# Sheet.net
KiCad netlist of a schematic drawn in Altium Designer
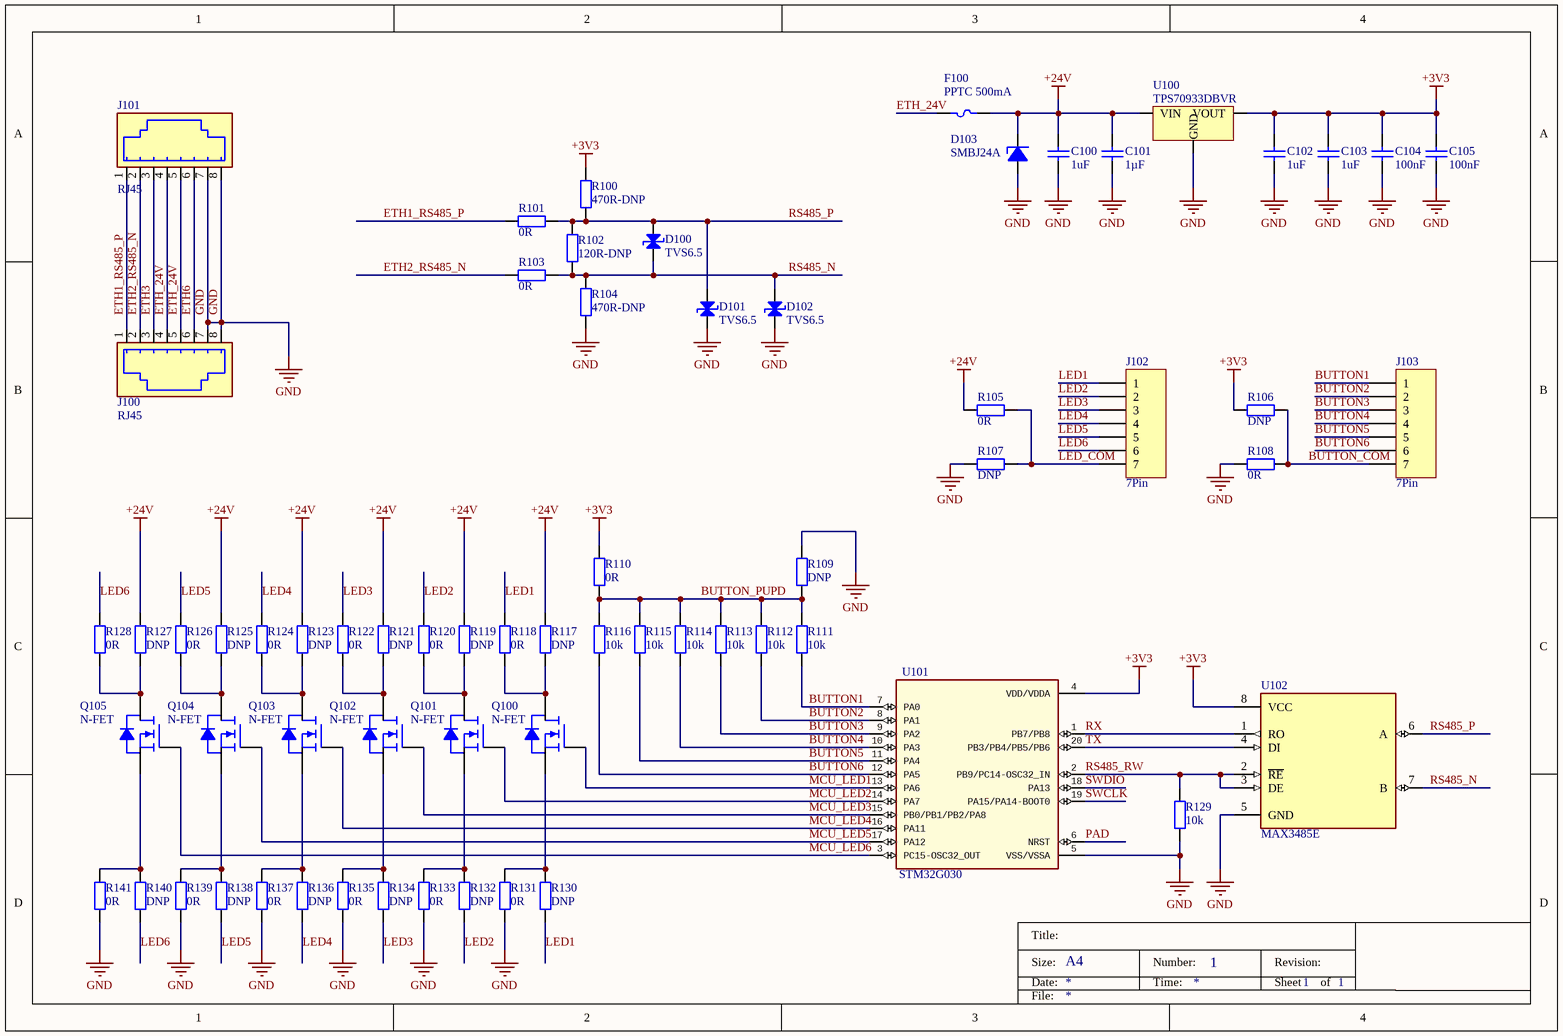
[diagram p0: Sheet.SchDoc]

(export (version "E")
  (design (tool "Eeschema 10.0.6"))
  (components
    (comp (ref "C100") (value "1uF") (footprint "C0603") (libsource (lib "Library") (part "Capacitor")))
    (comp (ref "C101") (value "1µF") (footprint "C0603") (libsource (lib "Library") (part "Capacitor")))
    (comp (ref "C102") (value "1uF") (footprint "C0603") (libsource (lib "Library") (part "Capacitor")))
    (comp (ref "C103") (value "1uF") (footprint "C0603") (libsource (lib "Library") (part "Capacitor")))
    (comp (ref "C104") (value "100nF") (footprint "C0603") (libsource (lib "Library") (part "Capacitor")))
    (comp (ref "C105") (value "100nF") (footprint "C0603") (libsource (lib "Library") (part "Capacitor")))
    (comp (ref "D100") (value "TVS6.5") (footprint "SOD323") (libsource (lib "Library") (part "TVS Bi")))
    (comp (ref "D101") (value "TVS6.5") (footprint "SOD323") (libsource (lib "Library") (part "TVS Bi")))
    (comp (ref "D102") (value "TVS6.5") (footprint "SOD323") (libsource (lib "Library") (part "TVS Bi")))
    (comp (ref "D103") (value "SMBJ24A") (footprint "SMB") (libsource (lib "Library") (part "TVS Uni")))
    (comp (ref "F100") (value "PPTC 500mA") (footprint "PPTC1812") (libsource (lib "Library") (part "Fuse")))
    (comp (ref "J100")
      (value "RJ45")
      (footprint "RJ45_RA")
      (description "Jack Modular Connector 8p8c (RJ45, Ethernet) Vertical Unshielded Cat5")
      (fields (field (name "MF") "Wurth Elektronik") (field (name "MP") "615008144221"))
      (libsource (lib "Library") (part "RJ45"))
    )
    (comp (ref "J101")
      (value "RJ45")
      (footprint "RJ45_RA")
      (description "Jack Modular Connector 8p8c (RJ45, Ethernet) Vertical Unshielded Cat5")
      (fields (field (name "MF") "Wurth Elektronik") (field (name "MP") "615008144221"))
      (libsource (lib "") (part "RJ45_1"))
    )
    (comp (ref "J102") (value "7Pin") (footprint "7Pin") (libsource (lib "Library") (part "7Pin")))
    (comp (ref "J103") (value "7Pin") (footprint "7Pin") (libsource (lib "Library") (part "7Pin")))
    (comp (ref "Q100") (value "N-FET") (footprint "SOT323") (libsource (lib "Library") (part "N-FET")))
    (comp (ref "Q101") (value "N-FET") (footprint "SOT323") (libsource (lib "Library") (part "N-FET")))
    (comp (ref "Q102") (value "N-FET") (footprint "SOT323") (libsource (lib "Library") (part "N-FET")))
    (comp (ref "Q103") (value "N-FET") (footprint "SOT323") (libsource (lib "Library") (part "N-FET")))
    (comp (ref "Q104") (value "N-FET") (footprint "SOT323") (libsource (lib "Library") (part "N-FET")))
    (comp (ref "Q105") (value "N-FET") (footprint "SOT323") (libsource (lib "Library") (part "N-FET")))
    (comp (ref "R100") (value "470R-DNP") (footprint "R0603") (libsource (lib "") (part "Resistor_1")))
    (comp (ref "R101") (value "0R") (footprint "R0603") (libsource (lib "Library") (part "Resistor")))
    (comp (ref "R102") (value "120R-DNP") (footprint "R0603") (libsource (lib "") (part "Resistor_1")))
    (comp (ref "R103") (value "0R") (footprint "R0603") (libsource (lib "Library") (part "Resistor")))
    (comp (ref "R104") (value "470R-DNP") (footprint "R0603") (libsource (lib "") (part "Resistor_1")))
    (comp (ref "R105") (value "0R") (footprint "R0603") (libsource (lib "") (part "Resistor_2")))
    (comp (ref "R106") (value "DNP") (footprint "R0603") (libsource (lib "") (part "Resistor_2")))
    (comp (ref "R107") (value "DNP") (footprint "R0603") (libsource (lib "") (part "Resistor_2")))
    (comp (ref "R108") (value "0R") (footprint "R0603") (libsource (lib "") (part "Resistor_2")))
    (comp (ref "R109") (value "DNP") (footprint "R0603") (libsource (lib "Library") (part "Resistor")))
    (comp (ref "R110") (value "0R") (footprint "R0603") (libsource (lib "Library") (part "Resistor")))
    (comp (ref "R111") (value "10k") (footprint "R0603") (libsource (lib "Library") (part "Resistor")))
    (comp (ref "R112") (value "10k") (footprint "R0603") (libsource (lib "Library") (part "Resistor")))
    (comp (ref "R113") (value "10k") (footprint "R0603") (libsource (lib "Library") (part "Resistor")))
    (comp (ref "R114") (value "10k") (footprint "R0603") (libsource (lib "Library") (part "Resistor")))
    (comp (ref "R115") (value "10k") (footprint "R0603") (libsource (lib "Library") (part "Resistor")))
    (comp (ref "R116") (value "10k") (footprint "R0603") (libsource (lib "Library") (part "Resistor")))
    (comp (ref "R117") (value "DNP") (footprint "R0603") (libsource (lib "Library") (part "Resistor")))
    (comp (ref "R118") (value "0R") (footprint "R0603") (libsource (lib "Library") (part "Resistor")))
    (comp (ref "R119") (value "DNP") (footprint "R0603") (libsource (lib "Library") (part "Resistor")))
    (comp (ref "R120") (value "0R") (footprint "R0603") (libsource (lib "Library") (part "Resistor")))
    (comp (ref "R121") (value "DNP") (footprint "R0603") (libsource (lib "Library") (part "Resistor")))
    (comp (ref "R122") (value "0R") (footprint "R0603") (libsource (lib "Library") (part "Resistor")))
    (comp (ref "R123") (value "DNP") (footprint "R0603") (libsource (lib "Library") (part "Resistor")))
    (comp (ref "R124") (value "0R") (footprint "R0603") (libsource (lib "Library") (part "Resistor")))
    (comp (ref "R125") (value "DNP") (footprint "R0603") (libsource (lib "Library") (part "Resistor")))
    (comp (ref "R126") (value "0R") (footprint "R0603") (libsource (lib "Library") (part "Resistor")))
    (comp (ref "R127") (value "DNP") (footprint "R0603") (libsource (lib "Library") (part "Resistor")))
    (comp (ref "R128") (value "0R") (footprint "R0603") (libsource (lib "Library") (part "Resistor")))
    (comp (ref "R129") (value "10k") (footprint "R0603") (libsource (lib "Library") (part "Resistor")))
    (comp (ref "R130") (value "DNP") (footprint "R0603") (libsource (lib "Library") (part "Resistor")))
    (comp (ref "R131") (value "0R") (footprint "R0603") (libsource (lib "Library") (part "Resistor")))
    (comp (ref "R132") (value "DNP") (footprint "R0603") (libsource (lib "Library") (part "Resistor")))
    (comp (ref "R133") (value "0R") (footprint "R0603") (libsource (lib "Library") (part "Resistor")))
    (comp (ref "R134") (value "DNP") (footprint "R0603") (libsource (lib "Library") (part "Resistor")))
    (comp (ref "R135") (value "0R") (footprint "R0603") (libsource (lib "Library") (part "Resistor")))
    (comp (ref "R136") (value "DNP") (footprint "R0603") (libsource (lib "Library") (part "Resistor")))
    (comp (ref "R137") (value "0R") (footprint "R0603") (libsource (lib "Library") (part "Resistor")))
    (comp (ref "R138") (value "DNP") (footprint "R0603") (libsource (lib "Library") (part "Resistor")))
    (comp (ref "R139") (value "0R") (footprint "R0603") (libsource (lib "Library") (part "Resistor")))
    (comp (ref "R140") (value "DNP") (footprint "R0603") (libsource (lib "Library") (part "Resistor")))
    (comp (ref "R141") (value "0R") (footprint "R0603") (libsource (lib "Library") (part "Resistor")))
    (comp (ref "U100")
      (value "TPS70933DBVR")
      (footprint "SOT-23-5")
      (fields (field (name "MP") "LP38690DT-5.0/NOPB") (field (name "MF") "Texas Instruments"))
      (libsource (lib "Schlib1") (part "LDO"))
    )
    (comp (ref "U101")
      (value "STM32G030")
      (footprint "TSSOP20")
      (fields
        (field (name "MANUFACTURER_PART_NUMBER") "STM32G030F6P6TR")
        (field (name "COPYRIGHT") "Copyright (C) 2022 Ultra Librarian. All rights reserved.")
      )
      (libsource (lib "Schlib1") (part "STM32G030"))
    )
    (comp (ref "U102")
      (value "MAX3485E")
      (footprint "SOIC-08")
      (description "1/1 Transceiver Half RS422, RS485 8-SOIC")
      (fields (field (name "MF") "Maxim Integrated") (field (name "MP") "MAX3485EESA+T"))
      (libsource (lib "Library") (part "MAX3485E"))
    )
  )
  (nets
    (net (code "1") (name "+3V3") (class "Default")
      (node (ref "C102") (pin "2") (pinfunction "2_2") (pintype "passive"))
      (node (ref "C103") (pin "2") (pinfunction "2_2") (pintype "passive"))
      (node (ref "C104") (pin "2") (pinfunction "2_2") (pintype "passive"))
      (node (ref "C105") (pin "2") (pinfunction "2_2") (pintype "passive"))
      (node (ref "R100") (pin "2") (pinfunction "2_2") (pintype "passive"))
      (node (ref "R106") (pin "2") (pinfunction "2_2") (pintype "passive"))
      (node (ref "R110") (pin "2") (pinfunction "2_2") (pintype "passive"))
      (node (ref "U100") (pin "5") (pinfunction "VOUT_5") (pintype "power_in"))
      (node (ref "U101") (pin "4") (pinfunction "VDD/VDDA_4") (pintype "power_in"))
      (node (ref "U102") (pin "8") (pinfunction "VCC_8") (pintype "power_in"))
    )
    (net (code "2") (name "+24V") (class "Default")
      (node (ref "C100") (pin "2") (pinfunction "2_2") (pintype "passive"))
      (node (ref "C101") (pin "2") (pinfunction "2_2") (pintype "passive"))
      (node (ref "D103") (pin "1") (pinfunction "1_1") (pintype "passive"))
      (node (ref "F100") (pin "2") (pinfunction "2_2") (pintype "passive"))
      (node (ref "R105") (pin "2") (pinfunction "2_2") (pintype "passive"))
      (node (ref "R117") (pin "2") (pinfunction "2_2") (pintype "passive"))
      (node (ref "R119") (pin "2") (pinfunction "2_2") (pintype "passive"))
      (node (ref "R121") (pin "2") (pinfunction "2_2") (pintype "passive"))
      (node (ref "R123") (pin "2") (pinfunction "2_2") (pintype "passive"))
      (node (ref "R125") (pin "2") (pinfunction "2_2") (pintype "passive"))
      (node (ref "R127") (pin "2") (pinfunction "2_2") (pintype "passive"))
      (node (ref "U100") (pin "1") (pinfunction "VIN_1") (pintype "power_in"))
    )
    (net (code "3") (name "/BUTTON1") (class "Default")
      (node (ref "J103") (pin "1") (pinfunction "1_1") (pintype "passive"))
      (node (ref "R111") (pin "1") (pinfunction "1_1") (pintype "passive"))
      (node (ref "U101") (pin "7") (pinfunction "PA0_7") (pintype "bidirectional"))
    )
    (net (code "4") (name "/BUTTON2") (class "Default")
      (node (ref "J103") (pin "2") (pinfunction "2_2") (pintype "passive"))
      (node (ref "R112") (pin "1") (pinfunction "1_1") (pintype "passive"))
      (node (ref "U101") (pin "8") (pinfunction "PA1_8") (pintype "bidirectional"))
    )
    (net (code "5") (name "/BUTTON3") (class "Default")
      (node (ref "J103") (pin "3") (pinfunction "3_3") (pintype "passive"))
      (node (ref "R113") (pin "1") (pinfunction "1_1") (pintype "passive"))
      (node (ref "U101") (pin "9") (pinfunction "PA2_9") (pintype "bidirectional"))
    )
    (net (code "6") (name "/BUTTON4") (class "Default")
      (node (ref "J103") (pin "4") (pinfunction "4_4") (pintype "passive"))
      (node (ref "R114") (pin "1") (pinfunction "1_1") (pintype "passive"))
      (node (ref "U101") (pin "10") (pinfunction "PA3_10") (pintype "bidirectional"))
    )
    (net (code "7") (name "/BUTTON5") (class "Default")
      (node (ref "J103") (pin "5") (pinfunction "5_5") (pintype "passive"))
      (node (ref "R115") (pin "1") (pinfunction "1_1") (pintype "passive"))
      (node (ref "U101") (pin "11") (pinfunction "PA4_11") (pintype "bidirectional"))
    )
    (net (code "8") (name "/BUTTON6") (class "Default")
      (node (ref "J103") (pin "6") (pinfunction "6_6") (pintype "passive"))
      (node (ref "R116") (pin "1") (pinfunction "1_1") (pintype "passive"))
      (node (ref "U101") (pin "12") (pinfunction "PA5_12") (pintype "bidirectional"))
    )
    (net (code "9") (name "/BUTTON_COM") (class "Default")
      (node (ref "J103") (pin "7") (pinfunction "7_7") (pintype "passive"))
      (node (ref "R106") (pin "1") (pinfunction "1_1") (pintype "passive"))
      (node (ref "R108") (pin "1") (pinfunction "1_1") (pintype "passive"))
    )
    (net (code "10") (name "/BUTTON_PUPD") (class "Default")
      (node (ref "R109") (pin "1") (pinfunction "1_1") (pintype "passive"))
      (node (ref "R110") (pin "1") (pinfunction "1_1") (pintype "passive"))
      (node (ref "R111") (pin "2") (pinfunction "2_2") (pintype "passive"))
      (node (ref "R112") (pin "2") (pinfunction "2_2") (pintype "passive"))
      (node (ref "R113") (pin "2") (pinfunction "2_2") (pintype "passive"))
      (node (ref "R114") (pin "2") (pinfunction "2_2") (pintype "passive"))
      (node (ref "R115") (pin "2") (pinfunction "2_2") (pintype "passive"))
      (node (ref "R116") (pin "2") (pinfunction "2_2") (pintype "passive"))
    )
    (net (code "11") (name "/ETH1_RS485_P") (class "Default")
      (node (ref "J100") (pin "1") (pinfunction "8_1") (pintype "passive"))
      (node (ref "J101") (pin "1") (pinfunction "8_1") (pintype "passive"))
      (node (ref "R101") (pin "1") (pinfunction "1_1") (pintype "passive"))
    )
    (net (code "12") (name "/ETH2_RS485_N") (class "Default")
      (node (ref "J100") (pin "2") (pinfunction "7_2") (pintype "passive"))
      (node (ref "J101") (pin "2") (pinfunction "7_2") (pintype "passive"))
      (node (ref "R103") (pin "1") (pinfunction "1_1") (pintype "passive"))
    )
    (net (code "13") (name "/ETH3") (class "Default")
      (node (ref "J100") (pin "3") (pinfunction "6_3") (pintype "passive"))
      (node (ref "J101") (pin "3") (pinfunction "6_3") (pintype "passive"))
    )
    (net (code "14") (name "/ETH6") (class "Default")
      (node (ref "J100") (pin "6") (pinfunction "3_6") (pintype "passive"))
      (node (ref "J101") (pin "6") (pinfunction "3_6") (pintype "passive"))
    )
    (net (code "15") (name "/ETH_24V") (class "Default")
      (node (ref "F100") (pin "1") (pinfunction "1_1") (pintype "passive"))
      (node (ref "J100") (pin "4") (pinfunction "5_4") (pintype "passive"))
      (node (ref "J100") (pin "5") (pinfunction "4_5") (pintype "passive"))
      (node (ref "J101") (pin "4") (pinfunction "5_4") (pintype "passive"))
      (node (ref "J101") (pin "5") (pinfunction "4_5") (pintype "passive"))
    )
    (net (code "16") (name "/LED1") (class "Default")
      (node (ref "J102") (pin "1") (pinfunction "1_1") (pintype "passive"))
      (node (ref "R118") (pin "2") (pinfunction "2_2") (pintype "passive"))
      (node (ref "R130") (pin "1") (pinfunction "1_1") (pintype "passive"))
    )
    (net (code "17") (name "/LED2") (class "Default")
      (node (ref "J102") (pin "2") (pinfunction "2_2") (pintype "passive"))
      (node (ref "R120") (pin "2") (pinfunction "2_2") (pintype "passive"))
      (node (ref "R132") (pin "1") (pinfunction "1_1") (pintype "passive"))
    )
    (net (code "18") (name "/LED3") (class "Default")
      (node (ref "J102") (pin "3") (pinfunction "3_3") (pintype "passive"))
      (node (ref "R122") (pin "2") (pinfunction "2_2") (pintype "passive"))
      (node (ref "R134") (pin "1") (pinfunction "1_1") (pintype "passive"))
    )
    (net (code "19") (name "/LED4") (class "Default")
      (node (ref "J102") (pin "4") (pinfunction "4_4") (pintype "passive"))
      (node (ref "R124") (pin "2") (pinfunction "2_2") (pintype "passive"))
      (node (ref "R136") (pin "1") (pinfunction "1_1") (pintype "passive"))
    )
    (net (code "20") (name "/LED5") (class "Default")
      (node (ref "J102") (pin "5") (pinfunction "5_5") (pintype "passive"))
      (node (ref "R126") (pin "2") (pinfunction "2_2") (pintype "passive"))
      (node (ref "R138") (pin "1") (pinfunction "1_1") (pintype "passive"))
    )
    (net (code "21") (name "/LED6") (class "Default")
      (node (ref "J102") (pin "6") (pinfunction "6_6") (pintype "passive"))
      (node (ref "R128") (pin "2") (pinfunction "2_2") (pintype "passive"))
      (node (ref "R140") (pin "1") (pinfunction "1_1") (pintype "passive"))
    )
    (net (code "22") (name "/LED_COM") (class "Default")
      (node (ref "J102") (pin "7") (pinfunction "7_7") (pintype "passive"))
      (node (ref "R105") (pin "1") (pinfunction "1_1") (pintype "passive"))
      (node (ref "R107") (pin "1") (pinfunction "1_1") (pintype "passive"))
    )
    (net (code "23") (name "/MCU_LED1") (class "Default")
      (node (ref "Q100") (pin "1") (pinfunction "G_1") (pintype "passive"))
      (node (ref "U101") (pin "13") (pinfunction "PA6_13") (pintype "bidirectional"))
    )
    (net (code "24") (name "/MCU_LED2") (class "Default")
      (node (ref "Q101") (pin "1") (pinfunction "G_1") (pintype "passive"))
      (node (ref "U101") (pin "14") (pinfunction "PA7_14") (pintype "bidirectional"))
    )
    (net (code "25") (name "/MCU_LED3") (class "Default")
      (node (ref "Q102") (pin "1") (pinfunction "G_1") (pintype "passive"))
      (node (ref "U101") (pin "15") (pinfunction "PB0/PB1/PB2/PA8_15") (pintype "bidirectional"))
    )
    (net (code "26") (name "/MCU_LED4") (class "Default")
      (node (ref "Q103") (pin "1") (pinfunction "G_1") (pintype "passive"))
      (node (ref "U101") (pin "16") (pinfunction "PA11_16") (pintype "bidirectional"))
    )
    (net (code "27") (name "/MCU_LED5") (class "Default")
      (node (ref "Q104") (pin "1") (pinfunction "G_1") (pintype "passive"))
      (node (ref "U101") (pin "17") (pinfunction "PA12_17") (pintype "bidirectional"))
    )
    (net (code "28") (name "/MCU_LED6") (class "Default")
      (node (ref "Q105") (pin "1") (pinfunction "G_1") (pintype "passive"))
      (node (ref "U101") (pin "3") (pinfunction "PC15-OSC32_OUT_3") (pintype "bidirectional"))
    )
    (net (code "29") (name "/PAD") (class "Default")
      (node (ref "U101") (pin "6") (pinfunction "NRST_6") (pintype "bidirectional"))
    )
    (net (code "30") (name "/RS485_N") (class "Default")
      (node (ref "D100") (pin "1") (pinfunction "1_1") (pintype "passive"))
      (node (ref "D102") (pin "2") (pinfunction "2_2") (pintype "passive"))
      (node (ref "R102") (pin "1") (pinfunction "1_1") (pintype "passive"))
      (node (ref "R103") (pin "2") (pinfunction "2_2") (pintype "passive"))
      (node (ref "R104") (pin "2") (pinfunction "2_2") (pintype "passive"))
      (node (ref "U102") (pin "7") (pinfunction "B_7") (pintype "bidirectional"))
    )
    (net (code "31") (name "/RS485_P") (class "Default")
      (node (ref "D100") (pin "2") (pinfunction "2_2") (pintype "passive"))
      (node (ref "D101") (pin "2") (pinfunction "2_2") (pintype "passive"))
      (node (ref "R100") (pin "1") (pinfunction "1_1") (pintype "passive"))
      (node (ref "R101") (pin "2") (pinfunction "2_2") (pintype "passive"))
      (node (ref "R102") (pin "2") (pinfunction "2_2") (pintype "passive"))
      (node (ref "U102") (pin "6") (pinfunction "A_6") (pintype "bidirectional"))
    )
    (net (code "32") (name "/RS485_RW") (class "Default")
      (node (ref "R129") (pin "2") (pinfunction "2_2") (pintype "passive"))
      (node (ref "U101") (pin "2") (pinfunction "PB9/PC14-OSC32_IN_2") (pintype "bidirectional"))
      (node (ref "U102") (pin "2") (pinfunction "~{RE}_2") (pintype "input"))
      (node (ref "U102") (pin "3") (pinfunction "DE_3") (pintype "input"))
    )
    (net (code "33") (name "/RX") (class "Default")
      (node (ref "U101") (pin "1") (pinfunction "PB7/PB8_1") (pintype "bidirectional"))
      (node (ref "U102") (pin "1") (pinfunction "RO_1") (pintype "output"))
    )
    (net (code "34") (name "/SWCLK") (class "Default")
      (node (ref "U101") (pin "19") (pinfunction "PA15/PA14-BOOT0_19") (pintype "bidirectional"))
    )
    (net (code "35") (name "/SWDIO") (class "Default")
      (node (ref "U101") (pin "18") (pinfunction "PA13_18") (pintype "bidirectional"))
    )
    (net (code "36") (name "/TX") (class "Default")
      (node (ref "U101") (pin "20") (pinfunction "PB3/PB4/PB5/PB6_20") (pintype "bidirectional"))
      (node (ref "U102") (pin "4") (pinfunction "DI_4") (pintype "input"))
    )
    (net (code "37") (name "GND") (class "Default")
      (node (ref "C100") (pin "1") (pinfunction "1_1") (pintype "passive"))
      (node (ref "C101") (pin "1") (pinfunction "1_1") (pintype "passive"))
      (node (ref "C102") (pin "1") (pinfunction "1_1") (pintype "passive"))
      (node (ref "C103") (pin "1") (pinfunction "1_1") (pintype "passive"))
      (node (ref "C104") (pin "1") (pinfunction "1_1") (pintype "passive"))
      (node (ref "C105") (pin "1") (pinfunction "1_1") (pintype "passive"))
      (node (ref "D101") (pin "1") (pinfunction "1_1") (pintype "passive"))
      (node (ref "D102") (pin "1") (pinfunction "1_1") (pintype "passive"))
      (node (ref "D103") (pin "2") (pinfunction "2_2") (pintype "passive"))
      (node (ref "J100") (pin "7") (pinfunction "2_7") (pintype "passive"))
      (node (ref "J100") (pin "8") (pinfunction "1_8") (pintype "passive"))
      (node (ref "J101") (pin "7") (pinfunction "2_7") (pintype "passive"))
      (node (ref "J101") (pin "8") (pinfunction "1_8") (pintype "passive"))
      (node (ref "R104") (pin "1") (pinfunction "1_1") (pintype "passive"))
      (node (ref "R107") (pin "2") (pinfunction "2_2") (pintype "passive"))
      (node (ref "R108") (pin "2") (pinfunction "2_2") (pintype "passive"))
      (node (ref "R109") (pin "2") (pinfunction "2_2") (pintype "passive"))
      (node (ref "R129") (pin "1") (pinfunction "1_1") (pintype "passive"))
      (node (ref "R131") (pin "1") (pinfunction "1_1") (pintype "passive"))
      (node (ref "R133") (pin "1") (pinfunction "1_1") (pintype "passive"))
      (node (ref "R135") (pin "1") (pinfunction "1_1") (pintype "passive"))
      (node (ref "R137") (pin "1") (pinfunction "1_1") (pintype "passive"))
      (node (ref "R139") (pin "1") (pinfunction "1_1") (pintype "passive"))
      (node (ref "R141") (pin "1") (pinfunction "1_1") (pintype "passive"))
      (node (ref "U100") (pin "2") (pinfunction "GND_2") (pintype "passive"))
      (node (ref "U101") (pin "5") (pinfunction "VSS/VSSA_5") (pintype "power_in"))
      (node (ref "U102") (pin "5") (pinfunction "GND_5") (pintype "power_in"))
    )
    (net (code "38") (name "Net-(Q100-D)") (class "Default")
      (node (ref "Q100") (pin "3") (pinfunction "D_3") (pintype "passive"))
      (node (ref "R117") (pin "1") (pinfunction "1_1") (pintype "passive"))
      (node (ref "R118") (pin "1") (pinfunction "1_1") (pintype "passive"))
    )
    (net (code "39") (name "Net-(Q100-S)") (class "Default")
      (node (ref "Q100") (pin "2") (pinfunction "S_2") (pintype "passive"))
      (node (ref "R130") (pin "2") (pinfunction "2_2") (pintype "passive"))
      (node (ref "R131") (pin "2") (pinfunction "2_2") (pintype "passive"))
    )
    (net (code "40") (name "Net-(Q101-D)") (class "Default")
      (node (ref "Q101") (pin "3") (pinfunction "D_3") (pintype "passive"))
      (node (ref "R119") (pin "1") (pinfunction "1_1") (pintype "passive"))
      (node (ref "R120") (pin "1") (pinfunction "1_1") (pintype "passive"))
    )
    (net (code "41") (name "Net-(Q101-S)") (class "Default")
      (node (ref "Q101") (pin "2") (pinfunction "S_2") (pintype "passive"))
      (node (ref "R132") (pin "2") (pinfunction "2_2") (pintype "passive"))
      (node (ref "R133") (pin "2") (pinfunction "2_2") (pintype "passive"))
    )
    (net (code "42") (name "Net-(Q102-D)") (class "Default")
      (node (ref "Q102") (pin "3") (pinfunction "D_3") (pintype "passive"))
      (node (ref "R121") (pin "1") (pinfunction "1_1") (pintype "passive"))
      (node (ref "R122") (pin "1") (pinfunction "1_1") (pintype "passive"))
    )
    (net (code "43") (name "Net-(Q102-S)") (class "Default")
      (node (ref "Q102") (pin "2") (pinfunction "S_2") (pintype "passive"))
      (node (ref "R134") (pin "2") (pinfunction "2_2") (pintype "passive"))
      (node (ref "R135") (pin "2") (pinfunction "2_2") (pintype "passive"))
    )
    (net (code "44") (name "Net-(Q103-D)") (class "Default")
      (node (ref "Q103") (pin "3") (pinfunction "D_3") (pintype "passive"))
      (node (ref "R123") (pin "1") (pinfunction "1_1") (pintype "passive"))
      (node (ref "R124") (pin "1") (pinfunction "1_1") (pintype "passive"))
    )
    (net (code "45") (name "Net-(Q103-S)") (class "Default")
      (node (ref "Q103") (pin "2") (pinfunction "S_2") (pintype "passive"))
      (node (ref "R136") (pin "2") (pinfunction "2_2") (pintype "passive"))
      (node (ref "R137") (pin "2") (pinfunction "2_2") (pintype "passive"))
    )
    (net (code "46") (name "Net-(Q104-D)") (class "Default")
      (node (ref "Q104") (pin "3") (pinfunction "D_3") (pintype "passive"))
      (node (ref "R125") (pin "1") (pinfunction "1_1") (pintype "passive"))
      (node (ref "R126") (pin "1") (pinfunction "1_1") (pintype "passive"))
    )
    (net (code "47") (name "Net-(Q104-S)") (class "Default")
      (node (ref "Q104") (pin "2") (pinfunction "S_2") (pintype "passive"))
      (node (ref "R138") (pin "2") (pinfunction "2_2") (pintype "passive"))
      (node (ref "R139") (pin "2") (pinfunction "2_2") (pintype "passive"))
    )
    (net (code "48") (name "Net-(Q105-D)") (class "Default")
      (node (ref "Q105") (pin "3") (pinfunction "D_3") (pintype "passive"))
      (node (ref "R127") (pin "1") (pinfunction "1_1") (pintype "passive"))
      (node (ref "R128") (pin "1") (pinfunction "1_1") (pintype "passive"))
    )
    (net (code "49") (name "Net-(Q105-S)") (class "Default")
      (node (ref "Q105") (pin "2") (pinfunction "S_2") (pintype "passive"))
      (node (ref "R140") (pin "2") (pinfunction "2_2") (pintype "passive"))
      (node (ref "R141") (pin "2") (pinfunction "2_2") (pintype "passive"))
    )
  )
)
